# ATmega_MCU.net
KiCad netlist of a schematic drawn in Altium Designer
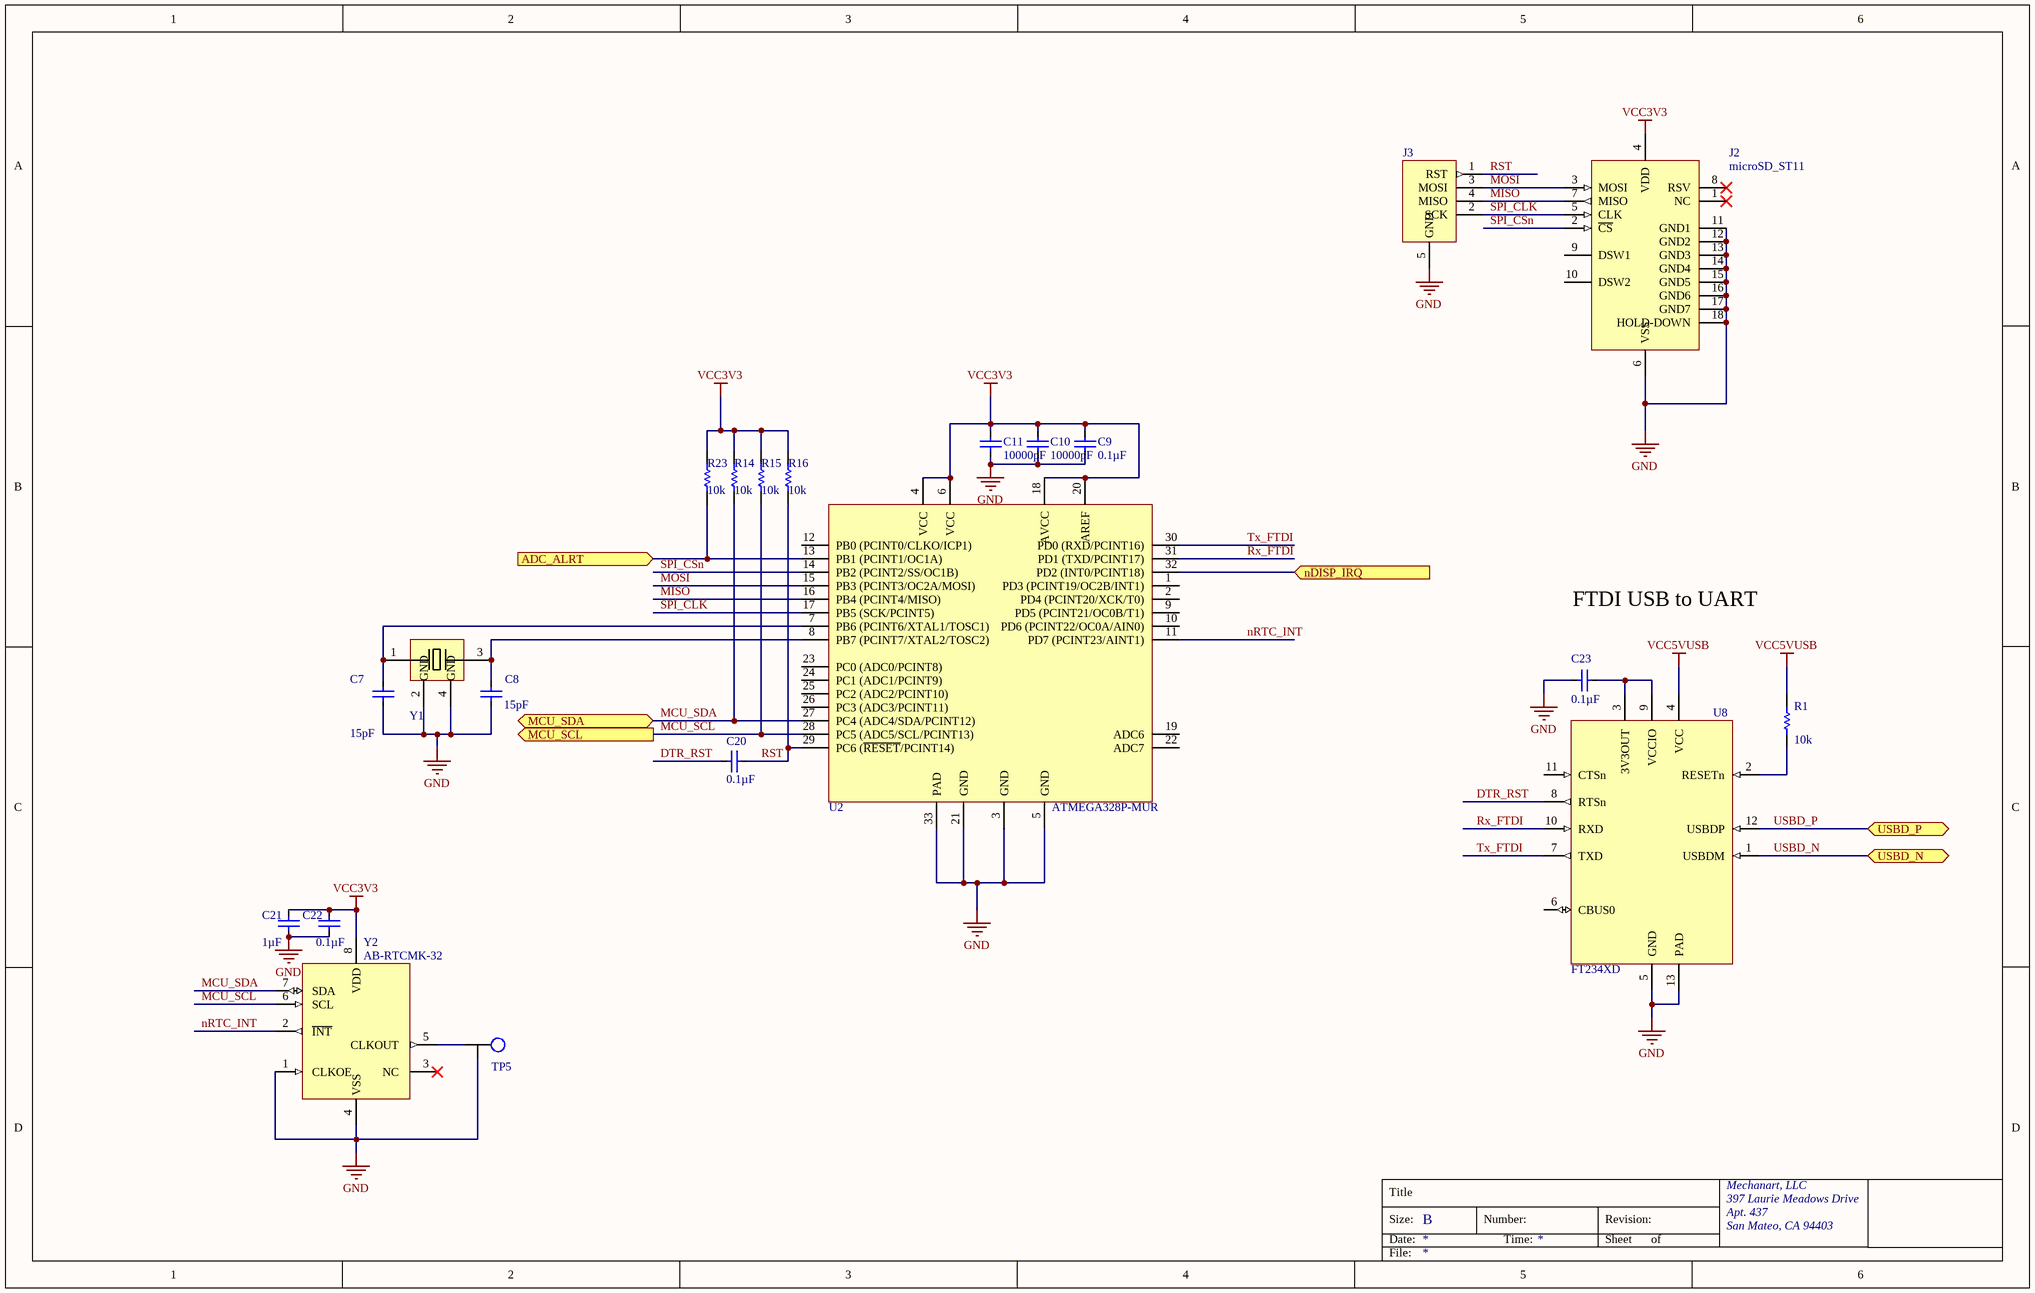
[diagram p0: ATmega_MCU.SchDoc]

(export (version "E")
  (design (tool "Eeschema 10.0.6"))
  (components
    (comp (ref "C7")
      (value "15pF")
      (footprint "CAPC0603X33L15L")
      (description "CAP CER 15PF 25V NP0 0201")
      (fields
        (field (name "MANUFACTURER") "Murata Electronics North America")
        (field (name "MANUFACTURER PART NUMBER") "GJM0335C1E150GB01D")
      )
      (libsource (lib "mechanart_oshw") (part "CapSMT"))
    )
    (comp (ref "C8")
      (value "15pF")
      (footprint "CAPC0603X33L15L")
      (description "CAP CER 15PF 25V NP0 0201")
      (fields
        (field (name "MANUFACTURER") "Murata Electronics North America")
        (field (name "MANUFACTURER PART NUMBER") "GJM0335C1E150GB01D")
      )
      (libsource (lib "mechanart_oshw") (part "CapSMT"))
    )
    (comp (ref "C9")
      (value "0.1µF")
      (footprint "CAPC1005X50L25N")
      (description "CAP CER 0.1UF 50V X7R 0402")
      (fields
        (field (name "MANUFACTURER") "Murata Electronics North America")
        (field (name "MANUFACTURER PART NUMBER") "GRM155R71H104KE14D")
      )
      (libsource (lib "mechanart_oshw") (part "CapSMT"))
    )
    (comp (ref "C10")
      (value "10000pF")
      (footprint "CAPC1005X50L25N")
      (description "CAP CER 10000PF 50V X7R 0402")
      (fields
        (field (name "MANUFACTURER") "Murata Electronics North America")
        (field (name "MANUFACTURER PART NUMBER") "GRM155R71H103KA88D")
      )
      (libsource (lib "mechanart_oshw") (part "CapSMT"))
    )
    (comp (ref "C11")
      (value "10000pF")
      (footprint "CAPC1005X50L25N")
      (description "CAP CER 10000PF 50V X7R 0402")
      (fields
        (field (name "MANUFACTURER") "Murata Electronics North America")
        (field (name "MANUFACTURER PART NUMBER") "GRM155R71H103KA88D")
      )
      (libsource (lib "mechanart_oshw") (part "CapSMT"))
    )
    (comp (ref "C20")
      (value "0.1µF")
      (footprint "CAPC1005X50L25N")
      (description "CAP CER 0.1UF 50V X7R 0402")
      (fields
        (field (name "MANUFACTURER") "Murata Electronics North America")
        (field (name "MANUFACTURER PART NUMBER") "GRM155R71H104KE14D")
      )
      (libsource (lib "mechanart_oshw") (part "CapSMT"))
    )
    (comp (ref "C21")
      (value "1µF")
      (footprint "CAPC1005X50L25N")
      (description "CAP CER 1UF 6.3V X7R 0402")
      (fields
        (field (name "MANUFACTURER") "Murata Electronics North America")
        (field (name "MANUFACTURER PART NUMBER") "GRM155R70J105KA12D")
      )
      (libsource (lib "mechanart_oshw") (part "CapSMT"))
    )
    (comp (ref "C22")
      (value "0.1µF")
      (footprint "CAPC1005X50L25N")
      (description "CAP CER 0.1UF 50V X7R 0402")
      (fields
        (field (name "MANUFACTURER") "Murata Electronics North America")
        (field (name "MANUFACTURER PART NUMBER") "GRM155R71H104KE14D")
      )
      (libsource (lib "mechanart_oshw") (part "CapSMT"))
    )
    (comp (ref "C23")
      (value "0.1µF")
      (footprint "CAPC1005X50L25N")
      (description "CAP CER 0.1UF 50V X7R 0402")
      (fields
        (field (name "MANUFACTURER") "Murata Electronics North America")
        (field (name "MANUFACTURER PART NUMBER") "GRM155R71H104KE14D")
      )
      (libsource (lib "mechanart_oshw") (part "CapSMT"))
    )
    (comp (ref "J2")
      (value "microSD_ST11")
      (footprint "microSD_ST11-H")
      (description "CONN MICRO SD CARD PUSH-PUSH R/A")
      (fields
        (field (name "MANUFACTURER") "JAE Electronics")
        (field (name "MANUFACTURER PART NUMBER") "ST11S008V4HR2000")
      )
      (libsource (lib "mechanart_oshw") (part "microSD_ST11"))
    )
    (comp (ref "J3")
      (value "POGO_SPI")
      (footprint "POGO_SPI")
      (description "5-pin SPI ISP pogo land with RST + GND")
      (libsource (lib "mechanart_oshw") (part "POGO_SPI"))
    )
    (comp (ref "R1")
      (value "10k")
      (footprint "RESC1608X45L30N")
      (description "RES 10K OHM 1/10W 5% 0603 SMD")
      (fields
        (field (name "MANUFACTURER") "Panasonic Electronic Components")
        (field (name "MANUFACTURER PART NUMBER") "ERJ-3GEYJ103V")
      )
      (libsource (lib "mechanart_oshw") (part "ResSMT"))
    )
    (comp (ref "R14")
      (value "10k")
      (footprint "RESC1005X40L25N")
      (description "RES SMD 10K OHM 5% 1/16W 0402")
      (fields
        (field (name "MANUFACTURER") "Vishay Dale")
        (field (name "MANUFACTURER PART NUMBER") "CRCW040210K0JNED")
      )
      (libsource (lib "mechanart_oshw") (part "ResSMT"))
    )
    (comp (ref "R15")
      (value "10k")
      (footprint "RESC1005X40L25N")
      (description "RES SMD 10K OHM 5% 1/16W 0402")
      (fields
        (field (name "MANUFACTURER") "Vishay Dale")
        (field (name "MANUFACTURER PART NUMBER") "CRCW040210K0JNED")
      )
      (libsource (lib "mechanart_oshw") (part "ResSMT"))
    )
    (comp (ref "R16")
      (value "10k")
      (footprint "RESC1005X40L25N")
      (description "RES SMD 10K OHM 5% 1/16W 0402")
      (fields
        (field (name "MANUFACTURER") "Vishay Dale")
        (field (name "MANUFACTURER PART NUMBER") "CRCW040210K0JNED")
      )
      (libsource (lib "mechanart_oshw") (part "ResSMT"))
    )
    (comp (ref "R23")
      (value "10k")
      (footprint "RESC1005X40L25N")
      (description "RES SMD 10K OHM 5% 1/16W 0402")
      (fields
        (field (name "MANUFACTURER") "Vishay Dale")
        (field (name "MANUFACTURER PART NUMBER") "CRCW040210K0JNED")
      )
      (libsource (lib "mechanart_oshw") (part "ResSMT"))
    )
    (comp (ref "TP5")
      (value "TPwGND")
      (footprint "TPwGND")
      (libsource (lib "mechanart_oshw") (part "TPwGND"))
    )
    (comp (ref "U2")
      (value "ATMEGA328P_32MLF")
      (footprint "QFN50P500X500X100-33T325X325L")
      (description "IC MCU 8BIT 32KB FLASH 32QFN")
      (fields
        (field (name "MANUFACTURER") "Atmel")
        (field (name "MANUFACTURER PART NUMBER") "ATMEGA328P-MUR")
      )
      (libsource (lib "mechanart_oshw") (part "ATMEGA328P_32MLF"))
    )
    (comp (ref "U8")
      (value "FT234XD")
      (footprint "SON13P45_300X300X80L40X23T250X160N")
      (description "IC USB SERIAL BASIC UART 12DFN")
      (fields
        (field (name "MANUFACTURER") "FTDI, Future Technology Devices International Ltd")
        (field (name "MANUFACTURER PART NUMBER") "FT234XD-R")
      )
      (libsource (lib "mechanart_oshw") (part "FT234XD"))
    )
    (comp (ref "Y1")
      (value "ABM11")
      (footprint "XTALDFN200X160X59-4L")
      (description "CRYSTAL 16.0000MHZ 10PF SMD")
      (fields
        (field (name "MANUFACTURER") "Abracon LLC")
        (field (name "MANUFACTURER PART NUMBER") "ABM11-16.000MHZ-B7G-T")
      )
      (libsource (lib "mechanart_oshw") (part "ABM11"))
    )
    (comp (ref "Y2")
      (value "AB-RTCMK-32")
      (footprint "SON100P320X250X100-8L")
      (description "IC RTC CLK/CALENDAR I2C 8-SMT")
      (fields
        (field (name "MANUFACTURER") "Abracon LLC")
        (field (name "MANUFACTURER PART NUMBER") "AB-RTCMK-32.768KHZ-T3")
      )
      (libsource (lib "mechanart_oshw") (part "AB-RTCMK-32"))
    )
  )
  (nets
    (net (code "1") (name "/ADC_ALRT") (class "Default")
      (node (ref "R23") (pin "1") (pinfunction "1_1") (pintype "passive"))
      (node (ref "U2") (pin "13") (pinfunction "PB1_(PCINT1/OC1A)_13") (pintype "passive"))
    )
    (net (code "2") (name "/DTR_RST") (class "Default")
      (node (ref "C20") (pin "1") (pinfunction "1_1") (pintype "passive"))
      (node (ref "U8") (pin "8") (pinfunction "RTSn_8") (pintype "output"))
    )
    (net (code "3") (name "/MCU_SCL") (class "Default")
      (node (ref "R15") (pin "1") (pinfunction "1_1") (pintype "passive"))
      (node (ref "U2") (pin "28") (pinfunction "PC5_(ADC5/SCL/PCINT13)_28") (pintype "passive"))
      (node (ref "Y2") (pin "6") (pinfunction "SCL_6") (pintype "input"))
    )
    (net (code "4") (name "/MCU_SDA") (class "Default")
      (node (ref "R14") (pin "1") (pinfunction "1_1") (pintype "passive"))
      (node (ref "U2") (pin "27") (pinfunction "PC4_(ADC4/SDA/PCINT12)_27") (pintype "passive"))
      (node (ref "Y2") (pin "7") (pinfunction "SDA_7") (pintype "bidirectional"))
    )
    (net (code "5") (name "/MISO") (class "Default")
      (node (ref "J2") (pin "7") (pinfunction "MISO_7") (pintype "output"))
      (node (ref "J3") (pin "4") (pinfunction "MISO_4") (pintype "passive"))
      (node (ref "U2") (pin "16") (pinfunction "PB4_(PCINT4/MISO)_16") (pintype "passive"))
    )
    (net (code "6") (name "/MOSI") (class "Default")
      (node (ref "J2") (pin "3") (pinfunction "MOSI_3") (pintype "input"))
      (node (ref "J3") (pin "3") (pinfunction "MOSI_3") (pintype "passive"))
      (node (ref "U2") (pin "15") (pinfunction "PB3_(PCINT3/OC2A/MOSI)_15") (pintype "passive"))
    )
    (net (code "7") (name "/RST") (class "Default")
      (node (ref "C20") (pin "2") (pinfunction "2_2") (pintype "passive"))
      (node (ref "J3") (pin "1") (pinfunction "RST_1") (pintype "output"))
      (node (ref "R16") (pin "1") (pinfunction "1_1") (pintype "passive"))
      (node (ref "U2") (pin "29") (pinfunction "PC6_(~{RESET}/PCINT14)_29") (pintype "passive"))
    )
    (net (code "8") (name "/Rx_FTDI") (class "Default")
      (node (ref "U2") (pin "31") (pinfunction "PD1_(TXD/PCINT17)_31") (pintype "passive"))
      (node (ref "U8") (pin "10") (pinfunction "RXD_10") (pintype "input"))
    )
    (net (code "9") (name "/SPI_CLK") (class "Default")
      (node (ref "J2") (pin "5") (pinfunction "CLK_5") (pintype "input"))
      (node (ref "J3") (pin "2") (pinfunction "SCK_2") (pintype "passive"))
      (node (ref "U2") (pin "17") (pinfunction "PB5_(SCK/PCINT5)_17") (pintype "passive"))
    )
    (net (code "10") (name "/SPI_CSn") (class "Default")
      (node (ref "J2") (pin "2") (pinfunction "~{CS}_2") (pintype "input"))
      (node (ref "U2") (pin "14") (pinfunction "PB2_(PCINT2/SS/OC1B)_14") (pintype "passive"))
    )
    (net (code "11") (name "/Tx_FTDI") (class "Default")
      (node (ref "U2") (pin "30") (pinfunction "PD0_(RXD/PCINT16)_30") (pintype "passive"))
      (node (ref "U8") (pin "7") (pinfunction "TXD_7") (pintype "output"))
    )
    (net (code "12") (name "/USBD_N") (class "Default")
      (node (ref "U8") (pin "1") (pinfunction "USBDM_1") (pintype "input"))
    )
    (net (code "13") (name "/USBD_P") (class "Default")
      (node (ref "U8") (pin "12") (pinfunction "USBDP_12") (pintype "input"))
    )
    (net (code "14") (name "/nDISP_IRQ") (class "Default")
      (node (ref "U2") (pin "32") (pinfunction "PD2_(INT0/PCINT18)_32") (pintype "passive"))
    )
    (net (code "15") (name "/nRTC_INT") (class "Default")
      (node (ref "U2") (pin "11") (pinfunction "PD7_(PCINT23/AINT1)_11") (pintype "passive"))
      (node (ref "Y2") (pin "2") (pinfunction "~{INT}_2") (pintype "output"))
    )
    (net (code "16") (name "GND") (class "Default")
      (node (ref "C10") (pin "2") (pinfunction "2_2") (pintype "passive"))
      (node (ref "C11") (pin "2") (pinfunction "2_2") (pintype "passive"))
      (node (ref "C21") (pin "2") (pinfunction "2_2") (pintype "passive"))
      (node (ref "C22") (pin "2") (pinfunction "2_2") (pintype "passive"))
      (node (ref "C23") (pin "1") (pinfunction "1_1") (pintype "passive"))
      (node (ref "C7") (pin "2") (pinfunction "2_2") (pintype "passive"))
      (node (ref "C8") (pin "2") (pinfunction "2_2") (pintype "passive"))
      (node (ref "C9") (pin "2") (pinfunction "2_2") (pintype "passive"))
      (node (ref "J2") (pin "11") (pinfunction "GND1_11") (pintype "passive"))
      (node (ref "J2") (pin "12") (pinfunction "GND2_12") (pintype "passive"))
      (node (ref "J2") (pin "13") (pinfunction "GND3_13") (pintype "passive"))
      (node (ref "J2") (pin "14") (pinfunction "GND4_14") (pintype "passive"))
      (node (ref "J2") (pin "15") (pinfunction "GND5_15") (pintype "passive"))
      (node (ref "J2") (pin "16") (pinfunction "GND6_16") (pintype "passive"))
      (node (ref "J2") (pin "17") (pinfunction "GND7_17") (pintype "passive"))
      (node (ref "J2") (pin "18") (pinfunction "HOLD-DOWN_18") (pintype "passive"))
      (node (ref "J2") (pin "6") (pinfunction "VSS_6") (pintype "power_in"))
      (node (ref "J3") (pin "5") (pinfunction "GND_5") (pintype "power_in"))
      (node (ref "TP5") (pin "2") (pinfunction "GND_2") (pintype "passive"))
      (node (ref "U2") (pin "21") (pinfunction "GND_21") (pintype "power_in"))
      (node (ref "U2") (pin "3") (pinfunction "GND_3") (pintype "power_in"))
      (node (ref "U2") (pin "33") (pinfunction "PAD_33") (pintype "power_in"))
      (node (ref "U2") (pin "5") (pinfunction "GND_5") (pintype "power_in"))
      (node (ref "U8") (pin "13") (pinfunction "PAD_13") (pintype "power_in"))
      (node (ref "U8") (pin "5") (pinfunction "GND_5") (pintype "power_in"))
      (node (ref "Y1") (pin "2") (pinfunction "GND_2") (pintype "power_in"))
      (node (ref "Y1") (pin "4") (pinfunction "GND_4") (pintype "power_in"))
      (node (ref "Y2") (pin "1") (pinfunction "CLKOE_1") (pintype "input"))
      (node (ref "Y2") (pin "4") (pinfunction "VSS_4") (pintype "power_in"))
    )
    (net (code "17") (name "Net-(TP5-TP)") (class "Default")
      (node (ref "TP5") (pin "1") (pinfunction "TP_1") (pintype "passive"))
      (node (ref "Y2") (pin "5") (pinfunction "CLKOUT_5") (pintype "output"))
    )
    (net (code "18") (name "Net-(U2-PB6_(PCINT6{slash}XTAL1{slash}TOSC1))") (class "Default")
      (node (ref "C7") (pin "1") (pinfunction "1_1") (pintype "passive"))
      (node (ref "U2") (pin "7") (pinfunction "PB6_(PCINT6/XTAL1/TOSC1)_7") (pintype "passive"))
      (node (ref "Y1") (pin "1") (pinfunction "OSC1_1") (pintype "passive"))
    )
    (net (code "19") (name "Net-(U2-PB7_(PCINT7{slash}XTAL2{slash}TOSC2))") (class "Default")
      (node (ref "C8") (pin "1") (pinfunction "1_1") (pintype "passive"))
      (node (ref "U2") (pin "8") (pinfunction "PB7_(PCINT7/XTAL2/TOSC2)_8") (pintype "passive"))
      (node (ref "Y1") (pin "3") (pinfunction "OSC2_3") (pintype "passive"))
    )
    (net (code "20") (name "Net-(U8-3V3OUT)") (class "Default")
      (node (ref "C23") (pin "2") (pinfunction "2_2") (pintype "passive"))
      (node (ref "U8") (pin "3") (pinfunction "3V3OUT_3") (pintype "power_in"))
      (node (ref "U8") (pin "9") (pinfunction "VCCIO_9") (pintype "power_in"))
    )
    (net (code "21") (name "Net-(U8-RESETn)") (class "Default")
      (node (ref "R1") (pin "1") (pinfunction "1_1") (pintype "passive"))
      (node (ref "U8") (pin "2") (pinfunction "RESETn_2") (pintype "input"))
    )
    (net (code "22") (name "VCC3V3") (class "Default")
      (node (ref "C10") (pin "1") (pinfunction "1_1") (pintype "passive"))
      (node (ref "C11") (pin "1") (pinfunction "1_1") (pintype "passive"))
      (node (ref "C21") (pin "1") (pinfunction "1_1") (pintype "passive"))
      (node (ref "C22") (pin "1") (pinfunction "1_1") (pintype "passive"))
      (node (ref "C9") (pin "1") (pinfunction "1_1") (pintype "passive"))
      (node (ref "J2") (pin "4") (pinfunction "VDD_4") (pintype "power_in"))
      (node (ref "R14") (pin "2") (pinfunction "2_2") (pintype "passive"))
      (node (ref "R15") (pin "2") (pinfunction "2_2") (pintype "passive"))
      (node (ref "R16") (pin "2") (pinfunction "2_2") (pintype "passive"))
      (node (ref "R23") (pin "2") (pinfunction "2_2") (pintype "passive"))
      (node (ref "U2") (pin "18") (pinfunction "AVCC_18") (pintype "power_in"))
      (node (ref "U2") (pin "20") (pinfunction "AREF_20") (pintype "passive"))
      (node (ref "U2") (pin "4") (pinfunction "VCC_4") (pintype "power_in"))
      (node (ref "U2") (pin "6") (pinfunction "VCC_6") (pintype "power_in"))
      (node (ref "Y2") (pin "8") (pinfunction "VDD_8") (pintype "power_in"))
    )
    (net (code "23") (name "VCC5VUSB") (class "Default")
      (node (ref "R1") (pin "2") (pinfunction "2_2") (pintype "passive"))
      (node (ref "U8") (pin "4") (pinfunction "VCC_4") (pintype "power_in"))
    )
    (net (code "24") (name "unconnected-(J2-DSW1-Pad9)") (class "Default")
      (node (ref "J2") (pin "9") (pinfunction "DSW1_9") (pintype "passive"))
    )
    (net (code "25") (name "unconnected-(J2-DSW2-Pad10)") (class "Default")
      (node (ref "J2") (pin "10") (pinfunction "DSW2_10") (pintype "passive"))
    )
    (net (code "26") (name "unconnected-(J2-NC-Pad1)") (class "Default")
      (node (ref "J2") (pin "1") (pinfunction "NC_1") (pintype "passive+no_connect"))
    )
    (net (code "27") (name "unconnected-(J2-RSV-Pad8)") (class "Default")
      (node (ref "J2") (pin "8") (pinfunction "RSV_8") (pintype "passive+no_connect"))
    )
    (net (code "28") (name "unconnected-(U2-ADC6-Pad19)") (class "Default")
      (node (ref "U2") (pin "19") (pinfunction "ADC6_19") (pintype "passive"))
    )
    (net (code "29") (name "unconnected-(U2-ADC7-Pad22)") (class "Default")
      (node (ref "U2") (pin "22") (pinfunction "ADC7_22") (pintype "passive"))
    )
    (net (code "30") (name "unconnected-(U2-PB0_(PCINT0{slash}CLKO{slash}ICP1)-Pad12)") (class "Default")
      (node (ref "U2") (pin "12") (pinfunction "PB0_(PCINT0/CLKO/ICP1)_12") (pintype "passive"))
    )
    (net (code "31") (name "unconnected-(U2-PC0_(ADC0{slash}PCINT8)-Pad23)") (class "Default")
      (node (ref "U2") (pin "23") (pinfunction "PC0_(ADC0/PCINT8)_23") (pintype "passive"))
    )
    (net (code "32") (name "unconnected-(U2-PC1_(ADC1{slash}PCINT9)-Pad24)") (class "Default")
      (node (ref "U2") (pin "24") (pinfunction "PC1_(ADC1/PCINT9)_24") (pintype "passive"))
    )
    (net (code "33") (name "unconnected-(U2-PC2_(ADC2{slash}PCINT10)-Pad25)") (class "Default")
      (node (ref "U2") (pin "25") (pinfunction "PC2_(ADC2/PCINT10)_25") (pintype "passive"))
    )
    (net (code "34") (name "unconnected-(U2-PC3_(ADC3{slash}PCINT11)-Pad26)") (class "Default")
      (node (ref "U2") (pin "26") (pinfunction "PC3_(ADC3/PCINT11)_26") (pintype "passive"))
    )
    (net (code "35") (name "unconnected-(U2-PD3_(PCINT19{slash}OC2B{slash}INT1)-Pad1)") (class "Default")
      (node (ref "U2") (pin "1") (pinfunction "PD3_(PCINT19/OC2B/INT1)_1") (pintype "passive"))
    )
    (net (code "36") (name "unconnected-(U2-PD4_(PCINT20{slash}XCK{slash}T0)-Pad2)") (class "Default")
      (node (ref "U2") (pin "2") (pinfunction "PD4_(PCINT20/XCK/T0)_2") (pintype "passive"))
    )
    (net (code "37") (name "unconnected-(U2-PD5_(PCINT21{slash}OC0B{slash}T1)-Pad9)") (class "Default")
      (node (ref "U2") (pin "9") (pinfunction "PD5_(PCINT21/OC0B/T1)_9") (pintype "passive"))
    )
    (net (code "38") (name "unconnected-(U2-PD6_(PCINT22{slash}OC0A{slash}AIN0)-Pad10)") (class "Default")
      (node (ref "U2") (pin "10") (pinfunction "PD6_(PCINT22/OC0A/AIN0)_10") (pintype "passive"))
    )
    (net (code "39") (name "unconnected-(U8-CBUS0-Pad6)") (class "Default")
      (node (ref "U8") (pin "6") (pinfunction "CBUS0_6") (pintype "bidirectional"))
    )
    (net (code "40") (name "unconnected-(U8-CTSn-Pad11)") (class "Default")
      (node (ref "U8") (pin "11") (pinfunction "CTSn_11") (pintype "input"))
    )
    (net (code "41") (name "unconnected-(Y2-NC-Pad3)") (class "Default")
      (node (ref "Y2") (pin "3") (pinfunction "NC_3") (pintype "passive+no_connect"))
    )
  )
)
